# MCU.net
KiCad netlist of a schematic drawn in Altium Designer
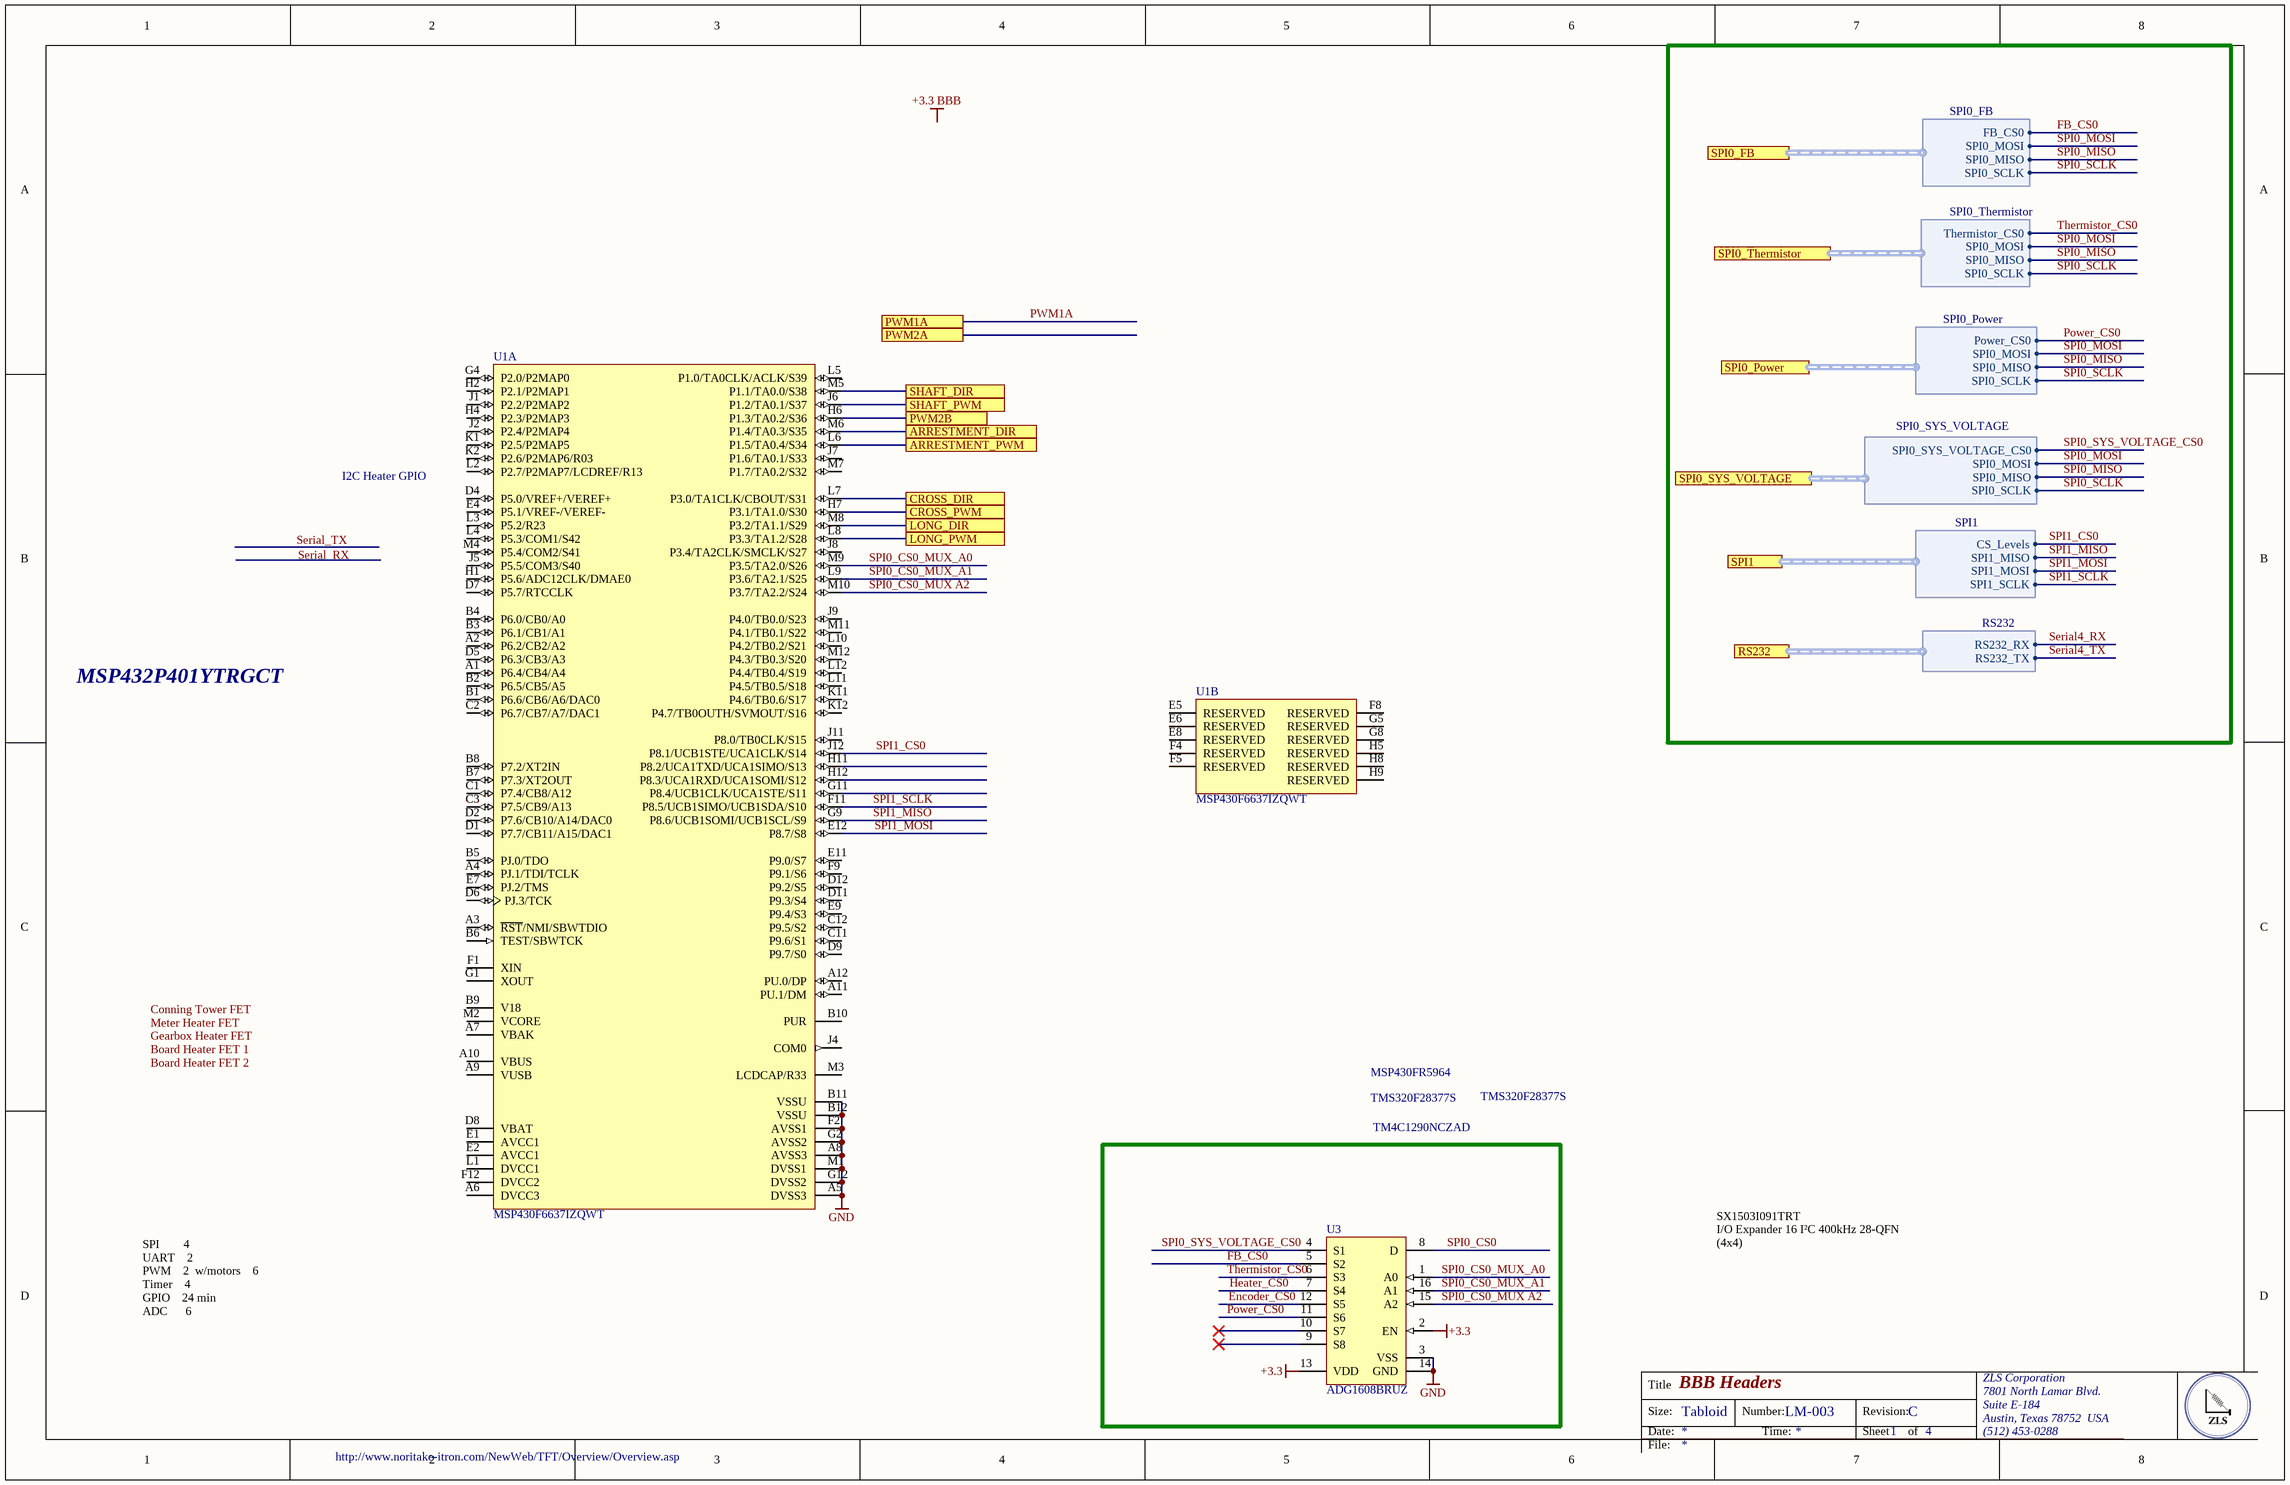
[diagram p0: MCU.SchDoc]

(export (version "E")
  (design (tool "Eeschema 10.0.6"))
  (components
    (comp (ref "U1")
      (value "MSP430F6637IZQWT")
      (footprint "TI-ZQW113")
      (fields (field (name "MANUFACTURER") "Texas Instruments"))
      (libsource (lib "Altium Content Vault") (part "TI-MSP430F663X-ZQW113_A"))
    )
    (comp (ref "U3")
      (value "ADG1608BRUZ")
      (footprint "ADI-RU-16_M")
      (description "4.5 Ohm Ron, 8-Channel +/-5 V,+12 V, +5 V and +3.3 V Multiplexer, 16-pin SOP (RU-16), Tube")
      (fields (field (name "MANUFACTURER") "Analog Devices Inc.") (field (name "BASE PART NUMBER") "ADG1608"))
      (libsource (lib "Altium Content Vault") (part "CMP-0793-00136-1"))
    )
  )
  (nets
    (net (code "7") (name "+3.3") (class "Default")
      (node (ref "U3") (pin "13") (pinfunction "VDD_13") (pintype "power_in"))
      (node (ref "U3") (pin "2") (pinfunction "EN_2") (pintype "input"))
    )
    (net (code "9") (name "/ARRESTMENT_DIR") (class "Default")
      (node (ref "U1") (pin "M6") (pinfunction "P1.4/TA0.3/S35_M6") (pintype "bidirectional"))
    )
    (net (code "10") (name "/ARRESTMENT_PWM") (class "Default")
      (node (ref "U1") (pin "L6") (pinfunction "P1.5/TA0.4/S34_L6") (pintype "bidirectional"))
    )
    (net (code "13") (name "/CROSS_DIR") (class "Default")
      (node (ref "U1") (pin "L7") (pinfunction "P3.0/TA1CLK/CBOUT/S31_L7") (pintype "bidirectional"))
    )
    (net (code "14") (name "/CROSS_PWM") (class "Default")
      (node (ref "U1") (pin "H7") (pinfunction "P3.1/TA1.0/S30_H7") (pintype "bidirectional"))
    )
    (net (code "16") (name "/Encoder_CS0") (class "Default")
      (node (ref "U3") (pin "12") (pinfunction "S5_12") (pintype "passive"))
    )
    (net (code "17") (name "/FB_CS0") (class "Default")
      (node (ref "U3") (pin "5") (pinfunction "S2_5") (pintype "passive"))
    )
    (net (code "19") (name "/Heater_CS0") (class "Default")
      (node (ref "U3") (pin "7") (pinfunction "S4_7") (pintype "passive"))
    )
    (net (code "20") (name "/LONG_DIR") (class "Default")
      (node (ref "U1") (pin "M8") (pinfunction "P3.2/TA1.1/S29_M8") (pintype "bidirectional"))
    )
    (net (code "21") (name "/LONG_PWM") (class "Default")
      (node (ref "U1") (pin "L8") (pinfunction "P3.3/TA1.2/S28_L8") (pintype "bidirectional"))
    )
    (net (code "25") (name "/PWM2B") (class "Default")
      (node (ref "U1") (pin "H6") (pinfunction "P1.3/TA0.2/S36_H6") (pintype "bidirectional"))
    )
    (net (code "26") (name "/Power_CS0") (class "Default")
      (node (ref "U3") (pin "11") (pinfunction "S6_11") (pintype "passive"))
    )
    (net (code "27") (name "/SHAFT_DIR") (class "Default")
      (node (ref "U1") (pin "M5") (pinfunction "P1.1/TA0.0/S38_M5") (pintype "bidirectional"))
    )
    (net (code "28") (name "/SHAFT_PWM") (class "Default")
      (node (ref "U1") (pin "J6") (pinfunction "P1.2/TA0.1/S37_J6") (pintype "bidirectional"))
    )
    (net (code "29") (name "/SPI0_CS0") (class "Default")
      (node (ref "U3") (pin "8") (pinfunction "D_8") (pintype "passive"))
    )
    (net (code "30") (name "/SPI0_CS0_MUX A2") (class "Default")
      (node (ref "U1") (pin "M10") (pinfunction "P3.7/TA2.2/S24_M10") (pintype "bidirectional"))
      (node (ref "U3") (pin "15") (pinfunction "A2_15") (pintype "input"))
    )
    (net (code "31") (name "/SPI0_CS0_MUX_A0") (class "Default")
      (node (ref "U1") (pin "M9") (pinfunction "P3.5/TA2.0/S26_M9") (pintype "bidirectional"))
      (node (ref "U3") (pin "1") (pinfunction "A0_1") (pintype "input"))
    )
    (net (code "32") (name "/SPI0_CS0_MUX_A1") (class "Default")
      (node (ref "U1") (pin "L9") (pinfunction "P3.6/TA2.1/S25_L9") (pintype "bidirectional"))
      (node (ref "U3") (pin "16") (pinfunction "A1_16") (pintype "input"))
    )
    (net (code "36") (name "/SPI0_SYS_VOLTAGE_CS0") (class "Default")
      (node (ref "U3") (pin "4") (pinfunction "S1_4") (pintype "passive"))
    )
    (net (code "37") (name "/SPI1_CS0") (class "Default")
      (node (ref "U1") (pin "J12") (pinfunction "P8.1/UCB1STE/UCA1CLK/S14_J12") (pintype "bidirectional"))
    )
    (net (code "38") (name "/SPI1_MISO") (class "Default")
      (node (ref "U1") (pin "G9") (pinfunction "P8.6/UCB1SOMI/UCB1SCL/S9_G9") (pintype "bidirectional"))
    )
    (net (code "39") (name "/SPI1_MOSI") (class "Default")
      (node (ref "U1") (pin "E12") (pinfunction "P8.7/S8_E12") (pintype "bidirectional"))
    )
    (net (code "40") (name "/SPI1_SCLK") (class "Default")
      (node (ref "U1") (pin "F11") (pinfunction "P8.5/UCB1SIMO/UCB1SDA/S10_F11") (pintype "bidirectional"))
    )
    (net (code "45") (name "/Thermistor_CS0") (class "Default")
      (node (ref "U3") (pin "6") (pinfunction "S3_6") (pintype "passive"))
    )
    (net (code "52") (name "GND") (class "Default")
      (node (ref "U1") (pin "A5") (pinfunction "DVSS3_A5") (pintype "power_in"))
      (node (ref "U1") (pin "A8") (pinfunction "AVSS3_A8") (pintype "power_in"))
      (node (ref "U1") (pin "B11") (pinfunction "VSSU_B11") (pintype "power_in"))
      (node (ref "U1") (pin "B12") (pinfunction "VSSU_B12") (pintype "power_in"))
      (node (ref "U1") (pin "F2") (pinfunction "AVSS1_F2") (pintype "power_in"))
      (node (ref "U1") (pin "G12") (pinfunction "DVSS2_G12") (pintype "power_in"))
      (node (ref "U1") (pin "G2") (pinfunction "AVSS2_G2") (pintype "power_in"))
      (node (ref "U1") (pin "M1") (pinfunction "DVSS1_M1") (pintype "power_in"))
      (node (ref "U3") (pin "14") (pinfunction "GND_14") (pintype "power_in"))
      (node (ref "U3") (pin "3") (pinfunction "VSS_3") (pintype "power_in"))
    )
    (net (code "53") (name "unconnected-(U1A-AVCC1-PadE1)") (class "Default")
      (node (ref "U1") (pin "E1") (pinfunction "AVCC1_E1") (pintype "power_in"))
    )
    (net (code "54") (name "unconnected-(U1A-AVCC1-PadE2)") (class "Default")
      (node (ref "U1") (pin "E2") (pinfunction "AVCC1_E2") (pintype "power_in"))
    )
    (net (code "55") (name "unconnected-(U1A-COM0-PadJ4)") (class "Default")
      (node (ref "U1") (pin "J4") (pinfunction "COM0_J4") (pintype "output"))
    )
    (net (code "56") (name "unconnected-(U1A-DVCC1-PadL1)") (class "Default")
      (node (ref "U1") (pin "L1") (pinfunction "DVCC1_L1") (pintype "power_in"))
    )
    (net (code "57") (name "unconnected-(U1A-DVCC2-PadF12)") (class "Default")
      (node (ref "U1") (pin "F12") (pinfunction "DVCC2_F12") (pintype "power_in"))
    )
    (net (code "58") (name "unconnected-(U1A-DVCC3-PadA6)") (class "Default")
      (node (ref "U1") (pin "A6") (pinfunction "DVCC3_A6") (pintype "power_in"))
    )
    (net (code "59") (name "unconnected-(U1A-LCDCAP{slash}R33-PadM3)") (class "Default")
      (node (ref "U1") (pin "M3") (pinfunction "LCDCAP/R33_M3") (pintype "passive"))
    )
    (net (code "60") (name "unconnected-(U1A-P1.0{slash}TA0CLK{slash}ACLK{slash}S39-PadL5)") (class "Default")
      (node (ref "U1") (pin "L5") (pinfunction "P1.0/TA0CLK/ACLK/S39_L5") (pintype "bidirectional"))
    )
    (net (code "61") (name "unconnected-(U1A-P1.6{slash}TA0.1{slash}S33-PadJ7)") (class "Default")
      (node (ref "U1") (pin "J7") (pinfunction "P1.6/TA0.1/S33_J7") (pintype "bidirectional"))
    )
    (net (code "62") (name "unconnected-(U1A-P1.7{slash}TA0.2{slash}S32-PadM7)") (class "Default")
      (node (ref "U1") (pin "M7") (pinfunction "P1.7/TA0.2/S32_M7") (pintype "bidirectional"))
    )
    (net (code "63") (name "unconnected-(U1A-P2.0{slash}P2MAP0-PadG4)") (class "Default")
      (node (ref "U1") (pin "G4") (pinfunction "P2.0/P2MAP0_G4") (pintype "bidirectional"))
    )
    (net (code "64") (name "unconnected-(U1A-P2.1{slash}P2MAP1-PadH2)") (class "Default")
      (node (ref "U1") (pin "H2") (pinfunction "P2.1/P2MAP1_H2") (pintype "bidirectional"))
    )
    (net (code "65") (name "unconnected-(U1A-P2.2{slash}P2MAP2-PadJ1)") (class "Default")
      (node (ref "U1") (pin "J1") (pinfunction "P2.2/P2MAP2_J1") (pintype "bidirectional"))
    )
    (net (code "66") (name "unconnected-(U1A-P2.3{slash}P2MAP3-PadH4)") (class "Default")
      (node (ref "U1") (pin "H4") (pinfunction "P2.3/P2MAP3_H4") (pintype "bidirectional"))
    )
    (net (code "67") (name "unconnected-(U1A-P2.4{slash}P2MAP4-PadJ2)") (class "Default")
      (node (ref "U1") (pin "J2") (pinfunction "P2.4/P2MAP4_J2") (pintype "bidirectional"))
    )
    (net (code "68") (name "unconnected-(U1A-P2.5{slash}P2MAP5-PadK1)") (class "Default")
      (node (ref "U1") (pin "K1") (pinfunction "P2.5/P2MAP5_K1") (pintype "bidirectional"))
    )
    (net (code "69") (name "unconnected-(U1A-P2.6{slash}P2MAP6{slash}R03-PadK2)") (class "Default")
      (node (ref "U1") (pin "K2") (pinfunction "P2.6/P2MAP6/R03_K2") (pintype "bidirectional"))
    )
    (net (code "70") (name "unconnected-(U1A-P2.7{slash}P2MAP7{slash}LCDREF{slash}R13-PadL2)") (class "Default")
      (node (ref "U1") (pin "L2") (pinfunction "P2.7/P2MAP7/LCDREF/R13_L2") (pintype "bidirectional"))
    )
    (net (code "71") (name "unconnected-(U1A-P3.4{slash}TA2CLK{slash}SMCLK{slash}S27-PadJ8)") (class "Default")
      (node (ref "U1") (pin "J8") (pinfunction "P3.4/TA2CLK/SMCLK/S27_J8") (pintype "bidirectional"))
    )
    (net (code "72") (name "unconnected-(U1A-P4.0{slash}TB0.0{slash}S23-PadJ9)") (class "Default")
      (node (ref "U1") (pin "J9") (pinfunction "P4.0/TB0.0/S23_J9") (pintype "bidirectional"))
    )
    (net (code "73") (name "unconnected-(U1A-P4.1{slash}TB0.1{slash}S22-PadM11)") (class "Default")
      (node (ref "U1") (pin "M11") (pinfunction "P4.1/TB0.1/S22_M11") (pintype "bidirectional"))
    )
    (net (code "74") (name "unconnected-(U1A-P4.2{slash}TB0.2{slash}S21-PadL10)") (class "Default")
      (node (ref "U1") (pin "L10") (pinfunction "P4.2/TB0.2/S21_L10") (pintype "bidirectional"))
    )
    (net (code "75") (name "unconnected-(U1A-P4.3{slash}TB0.3{slash}S20-PadM12)") (class "Default")
      (node (ref "U1") (pin "M12") (pinfunction "P4.3/TB0.3/S20_M12") (pintype "bidirectional"))
    )
    (net (code "76") (name "unconnected-(U1A-P4.4{slash}TB0.4{slash}S19-PadL12)") (class "Default")
      (node (ref "U1") (pin "L12") (pinfunction "P4.4/TB0.4/S19_L12") (pintype "bidirectional"))
    )
    (net (code "77") (name "unconnected-(U1A-P4.5{slash}TB0.5{slash}S18-PadL11)") (class "Default")
      (node (ref "U1") (pin "L11") (pinfunction "P4.5/TB0.5/S18_L11") (pintype "bidirectional"))
    )
    (net (code "78") (name "unconnected-(U1A-P4.6{slash}TB0.6{slash}S17-PadK11)") (class "Default")
      (node (ref "U1") (pin "K11") (pinfunction "P4.6/TB0.6/S17_K11") (pintype "bidirectional"))
    )
    (net (code "79") (name "unconnected-(U1A-P4.7{slash}TB0OUTH{slash}SVMOUT{slash}S16-PadK12)") (class "Default")
      (node (ref "U1") (pin "K12") (pinfunction "P4.7/TB0OUTH/SVMOUT/S16_K12") (pintype "bidirectional"))
    )
    (net (code "80") (name "unconnected-(U1A-P5.0{slash}VREF+{slash}VEREF+-PadD4)") (class "Default")
      (node (ref "U1") (pin "D4") (pinfunction "P5.0/VREF+/VEREF+_D4") (pintype "bidirectional"))
    )
    (net (code "81") (name "unconnected-(U1A-P5.1{slash}VREF-{slash}VEREF--PadE4)") (class "Default")
      (node (ref "U1") (pin "E4") (pinfunction "P5.1/VREF-/VEREF-_E4") (pintype "bidirectional"))
    )
    (net (code "82") (name "unconnected-(U1A-P5.2{slash}R23-PadL3)") (class "Default")
      (node (ref "U1") (pin "L3") (pinfunction "P5.2/R23_L3") (pintype "bidirectional"))
    )
    (net (code "83") (name "unconnected-(U1A-P5.3{slash}COM1{slash}S42-PadL4)") (class "Default")
      (node (ref "U1") (pin "L4") (pinfunction "P5.3/COM1/S42_L4") (pintype "bidirectional"))
    )
    (net (code "84") (name "unconnected-(U1A-P5.4{slash}COM2{slash}S41-PadM4)") (class "Default")
      (node (ref "U1") (pin "M4") (pinfunction "P5.4/COM2/S41_M4") (pintype "bidirectional"))
    )
    (net (code "85") (name "unconnected-(U1A-P5.5{slash}COM3{slash}S40-PadJ5)") (class "Default")
      (node (ref "U1") (pin "J5") (pinfunction "P5.5/COM3/S40_J5") (pintype "bidirectional"))
    )
    (net (code "86") (name "unconnected-(U1A-P5.6{slash}ADC12CLK{slash}DMAE0-PadH1)") (class "Default")
      (node (ref "U1") (pin "H1") (pinfunction "P5.6/ADC12CLK/DMAE0_H1") (pintype "bidirectional"))
    )
    (net (code "87") (name "unconnected-(U1A-P5.7{slash}RTCCLK-PadD7)") (class "Default")
      (node (ref "U1") (pin "D7") (pinfunction "P5.7/RTCCLK_D7") (pintype "bidirectional"))
    )
    (net (code "88") (name "unconnected-(U1A-P6.0{slash}CB0{slash}A0-PadB4)") (class "Default")
      (node (ref "U1") (pin "B4") (pinfunction "P6.0/CB0/A0_B4") (pintype "bidirectional"))
    )
    (net (code "89") (name "unconnected-(U1A-P6.1{slash}CB1{slash}A1-PadB3)") (class "Default")
      (node (ref "U1") (pin "B3") (pinfunction "P6.1/CB1/A1_B3") (pintype "bidirectional"))
    )
    (net (code "90") (name "unconnected-(U1A-P6.2{slash}CB2{slash}A2-PadA2)") (class "Default")
      (node (ref "U1") (pin "A2") (pinfunction "P6.2/CB2/A2_A2") (pintype "bidirectional"))
    )
    (net (code "91") (name "unconnected-(U1A-P6.3{slash}CB3{slash}A3-PadD5)") (class "Default")
      (node (ref "U1") (pin "D5") (pinfunction "P6.3/CB3/A3_D5") (pintype "bidirectional"))
    )
    (net (code "92") (name "unconnected-(U1A-P6.4{slash}CB4{slash}A4-PadA1)") (class "Default")
      (node (ref "U1") (pin "A1") (pinfunction "P6.4/CB4/A4_A1") (pintype "bidirectional"))
    )
    (net (code "93") (name "unconnected-(U1A-P6.5{slash}CB5{slash}A5-PadB2)") (class "Default")
      (node (ref "U1") (pin "B2") (pinfunction "P6.5/CB5/A5_B2") (pintype "bidirectional"))
    )
    (net (code "94") (name "unconnected-(U1A-P6.6{slash}CB6{slash}A6{slash}DAC0-PadB1)") (class "Default")
      (node (ref "U1") (pin "B1") (pinfunction "P6.6/CB6/A6/DAC0_B1") (pintype "bidirectional"))
    )
    (net (code "95") (name "unconnected-(U1A-P6.7{slash}CB7{slash}A7{slash}DAC1-PadC2)") (class "Default")
      (node (ref "U1") (pin "C2") (pinfunction "P6.7/CB7/A7/DAC1_C2") (pintype "bidirectional"))
    )
    (net (code "96") (name "unconnected-(U1A-P7.2{slash}XT2IN-PadB8)") (class "Default")
      (node (ref "U1") (pin "B8") (pinfunction "P7.2/XT2IN_B8") (pintype "bidirectional"))
    )
    (net (code "97") (name "unconnected-(U1A-P7.3{slash}XT2OUT-PadB7)") (class "Default")
      (node (ref "U1") (pin "B7") (pinfunction "P7.3/XT2OUT_B7") (pintype "bidirectional"))
    )
    (net (code "98") (name "unconnected-(U1A-P7.4{slash}CB8{slash}A12-PadC1)") (class "Default")
      (node (ref "U1") (pin "C1") (pinfunction "P7.4/CB8/A12_C1") (pintype "bidirectional"))
    )
    (net (code "99") (name "unconnected-(U1A-P7.5{slash}CB9{slash}A13-PadC3)") (class "Default")
      (node (ref "U1") (pin "C3") (pinfunction "P7.5/CB9/A13_C3") (pintype "bidirectional"))
    )
    (net (code "100") (name "unconnected-(U1A-P7.6{slash}CB10{slash}A14{slash}DAC0-PadD2)") (class "Default")
      (node (ref "U1") (pin "D2") (pinfunction "P7.6/CB10/A14/DAC0_D2") (pintype "bidirectional"))
    )
    (net (code "101") (name "unconnected-(U1A-P7.7{slash}CB11{slash}A15{slash}DAC1-PadD1)") (class "Default")
      (node (ref "U1") (pin "D1") (pinfunction "P7.7/CB11/A15/DAC1_D1") (pintype "bidirectional"))
    )
    (net (code "102") (name "unconnected-(U1A-P8.0{slash}TB0CLK{slash}S15-PadJ11)") (class "Default")
      (node (ref "U1") (pin "J11") (pinfunction "P8.0/TB0CLK/S15_J11") (pintype "bidirectional"))
    )
    (net (code "103") (name "unconnected-(U1A-P8.2{slash}UCA1TXD{slash}UCA1SIMO{slash}S13-PadH11)") (class "Default")
      (node (ref "U1") (pin "H11") (pinfunction "P8.2/UCA1TXD/UCA1SIMO/S13_H11") (pintype "bidirectional"))
    )
    (net (code "104") (name "unconnected-(U1A-P8.3{slash}UCA1RXD{slash}UCA1SOMI{slash}S12-PadH12)") (class "Default")
      (node (ref "U1") (pin "H12") (pinfunction "P8.3/UCA1RXD/UCA1SOMI/S12_H12") (pintype "bidirectional"))
    )
    (net (code "105") (name "unconnected-(U1A-P8.4{slash}UCB1CLK{slash}UCA1STE{slash}S11-PadG11)") (class "Default")
      (node (ref "U1") (pin "G11") (pinfunction "P8.4/UCB1CLK/UCA1STE/S11_G11") (pintype "bidirectional"))
    )
    (net (code "106") (name "unconnected-(U1A-P9.0{slash}S7-PadE11)") (class "Default")
      (node (ref "U1") (pin "E11") (pinfunction "P9.0/S7_E11") (pintype "bidirectional"))
    )
    (net (code "107") (name "unconnected-(U1A-P9.1{slash}S6-PadF9)") (class "Default")
      (node (ref "U1") (pin "F9") (pinfunction "P9.1/S6_F9") (pintype "bidirectional"))
    )
    (net (code "108") (name "unconnected-(U1A-P9.2{slash}S5-PadD12)") (class "Default")
      (node (ref "U1") (pin "D12") (pinfunction "P9.2/S5_D12") (pintype "bidirectional"))
    )
    (net (code "109") (name "unconnected-(U1A-P9.3{slash}S4-PadD11)") (class "Default")
      (node (ref "U1") (pin "D11") (pinfunction "P9.3/S4_D11") (pintype "bidirectional"))
    )
    (net (code "110") (name "unconnected-(U1A-P9.4{slash}S3-PadE9)") (class "Default")
      (node (ref "U1") (pin "E9") (pinfunction "P9.4/S3_E9") (pintype "bidirectional"))
    )
    (net (code "111") (name "unconnected-(U1A-P9.5{slash}S2-PadC12)") (class "Default")
      (node (ref "U1") (pin "C12") (pinfunction "P9.5/S2_C12") (pintype "bidirectional"))
    )
    (net (code "112") (name "unconnected-(U1A-P9.6{slash}S1-PadC11)") (class "Default")
      (node (ref "U1") (pin "C11") (pinfunction "P9.6/S1_C11") (pintype "bidirectional"))
    )
    (net (code "113") (name "unconnected-(U1A-P9.7{slash}S0-PadD9)") (class "Default")
      (node (ref "U1") (pin "D9") (pinfunction "P9.7/S0_D9") (pintype "bidirectional"))
    )
    (net (code "114") (name "unconnected-(U1A-PJ.0{slash}TDO-PadB5)") (class "Default")
      (node (ref "U1") (pin "B5") (pinfunction "PJ.0/TDO_B5") (pintype "bidirectional"))
    )
    (net (code "115") (name "unconnected-(U1A-PJ.1{slash}TDI{slash}TCLK-PadA4)") (class "Default")
      (node (ref "U1") (pin "A4") (pinfunction "PJ.1/TDI/TCLK_A4") (pintype "bidirectional"))
    )
    (net (code "116") (name "unconnected-(U1A-PJ.2{slash}TMS-PadE7)") (class "Default")
      (node (ref "U1") (pin "E7") (pinfunction "PJ.2/TMS_E7") (pintype "bidirectional"))
    )
    (net (code "117") (name "unconnected-(U1A-PJ.3{slash}TCK-PadD6)") (class "Default")
      (node (ref "U1") (pin "D6") (pinfunction "PJ.3/TCK_D6") (pintype "bidirectional"))
    )
    (net (code "118") (name "unconnected-(U1A-PU.0{slash}DP-PadA12)") (class "Default")
      (node (ref "U1") (pin "A12") (pinfunction "PU.0/DP_A12") (pintype "bidirectional"))
    )
    (net (code "119") (name "unconnected-(U1A-PU.1{slash}DM-PadA11)") (class "Default")
      (node (ref "U1") (pin "A11") (pinfunction "PU.1/DM_A11") (pintype "bidirectional"))
    )
    (net (code "120") (name "unconnected-(U1A-PUR-PadB10)") (class "Default")
      (node (ref "U1") (pin "B10") (pinfunction "PUR_B10") (pintype "passive"))
    )
    (net (code "121") (name "unconnected-(U1A-TEST{slash}SBWTCK-PadB6)") (class "Default")
      (node (ref "U1") (pin "B6") (pinfunction "TEST/SBWTCK_B6") (pintype "input"))
    )
    (net (code "122") (name "unconnected-(U1A-V18-PadB9)") (class "Default")
      (node (ref "U1") (pin "B9") (pinfunction "V18_B9") (pintype "passive"))
    )
    (net (code "123") (name "unconnected-(U1A-VBAK-PadA7)") (class "Default")
      (node (ref "U1") (pin "A7") (pinfunction "VBAK_A7") (pintype "passive"))
    )
    (net (code "124") (name "unconnected-(U1A-VBAT-PadD8)") (class "Default")
      (node (ref "U1") (pin "D8") (pinfunction "VBAT_D8") (pintype "power_in"))
    )
    (net (code "125") (name "unconnected-(U1A-VBUS-PadA10)") (class "Default")
      (node (ref "U1") (pin "A10") (pinfunction "VBUS_A10") (pintype "power_in"))
    )
    (net (code "126") (name "unconnected-(U1A-VCORE-PadM2)") (class "Default")
      (node (ref "U1") (pin "M2") (pinfunction "VCORE_M2") (pintype "passive"))
    )
    (net (code "127") (name "unconnected-(U1A-VUSB-PadA9)") (class "Default")
      (node (ref "U1") (pin "A9") (pinfunction "VUSB_A9") (pintype "power_in"))
    )
    (net (code "128") (name "unconnected-(U1A-XIN-PadF1)") (class "Default")
      (node (ref "U1") (pin "F1") (pinfunction "XIN_F1") (pintype "passive"))
    )
    (net (code "129") (name "unconnected-(U1A-XOUT-PadG1)") (class "Default")
      (node (ref "U1") (pin "G1") (pinfunction "XOUT_G1") (pintype "passive"))
    )
    (net (code "130") (name "unconnected-(U1A-~{RST}{slash}NMI{slash}SBWTDIO-PadA3)") (class "Default")
      (node (ref "U1") (pin "A3") (pinfunction "~{RST}/NMI/SBWTDIO_A3") (pintype "bidirectional"))
    )
    (net (code "131") (name "unconnected-(U1B-RESERVED-PadE5)") (class "Default")
      (node (ref "U1") (pin "E5") (pinfunction "RESERVED_E5") (pintype "passive"))
    )
    (net (code "132") (name "unconnected-(U1B-RESERVED-PadE6)") (class "Default")
      (node (ref "U1") (pin "E6") (pinfunction "RESERVED_E6") (pintype "passive"))
    )
    (net (code "133") (name "unconnected-(U1B-RESERVED-PadE8)") (class "Default")
      (node (ref "U1") (pin "E8") (pinfunction "RESERVED_E8") (pintype "passive"))
    )
    (net (code "134") (name "unconnected-(U1B-RESERVED-PadF4)") (class "Default")
      (node (ref "U1") (pin "F4") (pinfunction "RESERVED_F4") (pintype "passive"))
    )
    (net (code "135") (name "unconnected-(U1B-RESERVED-PadF5)") (class "Default")
      (node (ref "U1") (pin "F5") (pinfunction "RESERVED_F5") (pintype "passive"))
    )
    (net (code "136") (name "unconnected-(U1B-RESERVED-PadF8)") (class "Default")
      (node (ref "U1") (pin "F8") (pinfunction "RESERVED_F8") (pintype "passive"))
    )
    (net (code "137") (name "unconnected-(U1B-RESERVED-PadG5)") (class "Default")
      (node (ref "U1") (pin "G5") (pinfunction "RESERVED_G5") (pintype "passive"))
    )
    (net (code "138") (name "unconnected-(U1B-RESERVED-PadG8)") (class "Default")
      (node (ref "U1") (pin "G8") (pinfunction "RESERVED_G8") (pintype "passive"))
    )
    (net (code "139") (name "unconnected-(U1B-RESERVED-PadH5)") (class "Default")
      (node (ref "U1") (pin "H5") (pinfunction "RESERVED_H5") (pintype "passive"))
    )
    (net (code "140") (name "unconnected-(U1B-RESERVED-PadH8)") (class "Default")
      (node (ref "U1") (pin "H8") (pinfunction "RESERVED_H8") (pintype "passive"))
    )
    (net (code "141") (name "unconnected-(U1B-RESERVED-PadH9)") (class "Default")
      (node (ref "U1") (pin "H9") (pinfunction "RESERVED_H9") (pintype "passive"))
    )
    (net (code "142") (name "unconnected-(U3-S7-Pad10)") (class "Default")
      (node (ref "U3") (pin "10") (pinfunction "S7_10") (pintype "passive+no_connect"))
    )
    (net (code "143") (name "unconnected-(U3-S8-Pad9)") (class "Default")
      (node (ref "U3") (pin "9") (pinfunction "S8_9") (pintype "passive+no_connect"))
    )
  )
)
